# Charge.net
KiCad netlist of a schematic drawn in Altium Designer
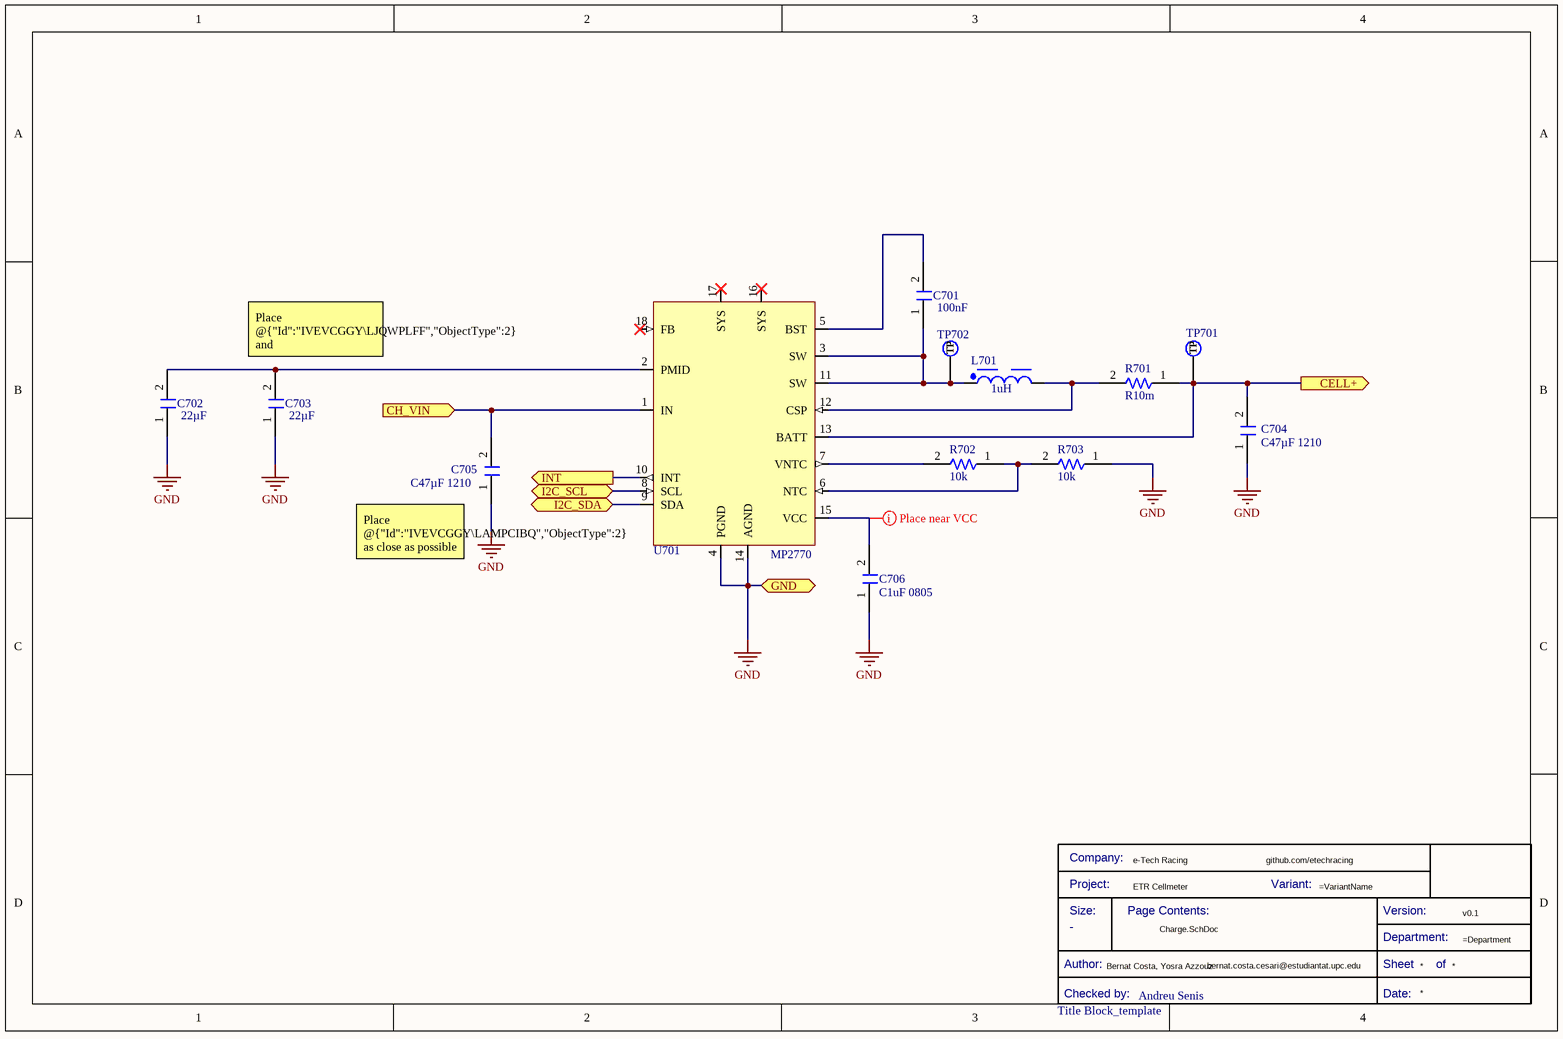
[diagram p0: Charge.SchDoc]

(export (version "E")
  (design (tool "Eeschema 10.0.6"))
  (components
    (comp (ref "*")
      (value "Title Block_template")
      (description "Standard Title Block")
      (fields
        (field (name "SIZE") "-")
        (field (name ".CREATOR") "GP")
        (field (name ".SCHCHECK") "GP")
        (field (name ".PCBCHECK") "GP")
      )
      (libsource (lib "EMEA- E-Tech Racing- I'Escola d'Enginyeria de Barcelona Est") (part "Title Block_template"))
    )
    (comp (ref "C701")
      (value "100nF")
      (footprint "CAPC1608X92X38LL15T08")
      (fields (field (name "Comment") "C100nF-25V-0603"))
      (libsource (lib "EMEA- E-Tech Racing- I'Escola d'Enginyeria de Barcelona Est") (part "C100p-50V-0805FNPC-C0G/NP0"))
    )
    (comp (ref "C702")
      (value "22µF")
      (footprint "WCAP-CSGP_0805_L2W1.25H0.8_Reflow")
      (fields (field (name "Comment") "C22uF-25V-0805"))
      (libsource (lib "EMEA- E-Tech Racing- I'Escola d'Enginyeria de Barcelona Est") (part "C100p-50V-0805FNPC-C0G/NP0"))
    )
    (comp (ref "C703")
      (value "22µF")
      (footprint "WCAP-CSGP_0805_L2W1.25H0.8_Reflow")
      (fields (field (name "Comment") "C22uF-25V-0805"))
      (libsource (lib "EMEA- E-Tech Racing- I'Escola d'Enginyeria de Barcelona Est") (part "C100p-50V-0805FNPC-C0G/NP0"))
    )
    (comp (ref "C704")
      (value "C47µF 1210")
      (footprint "FP-GRM32E-0_3-0_2-IPC_C")
      (libsource (lib "EMEA- E-Tech Racing- I'Escola d'Enginyeria de Barcelona Est") (part "C100p-50V-0805FNPC-C0G/NP0"))
    )
    (comp (ref "C705")
      (value "C47µF 1210")
      (footprint "FP-GRM32E-0_3-0_2-IPC_C")
      (libsource (lib "EMEA- E-Tech Racing- I'Escola d'Enginyeria de Barcelona Est") (part "C100p-50V-0805FNPC-C0G/NP0"))
    )
    (comp (ref "C706")
      (value "C1uF 0805")
      (footprint "WCAP-CSGP_0805_L2W1.25H1.25")
      (libsource (lib "EMEA- E-Tech Racing- I'Escola d'Enginyeria de Barcelona Est") (part "C100p-50V-0805FNPC-C0G/NP0"))
    )
    (comp (ref "L701")
      (value "1uH")
      (footprint "WE-PD_7345")
      (description "General Purpose Inductor, 1uH, 40%, 1 Element, Ferrite-Core, SMD, 2929. PN: 744777001")
      (fields (field (name "TOLERANCE") "40%") (field (name "Comment") "L1uH_120V_8A"))
      (libsource (lib "EMEA- E-Tech Racing- I'Escola d'Enginyeria de Barcelona Est") (part "Inductor - 2"))
    )
    (comp (ref "R701")
      (value "R10m")
      (footprint "WRIS-RSKS_1206_Wave")
      (fields
        (field (name "POWER") "250mW")
        (field (name "TOLERANCE") "1%")
        (field (name "Comment") "R10m-1206")
      )
      (libsource (lib "EMEA- E-Tech Racing- I'Escola d'Enginyeria de Barcelona Est") (part "R9.09K-1206FTK"))
    )
    (comp (ref "R702")
      (value "10k")
      (footprint "R0805FTK")
      (fields
        (field (name "TOLERANCE") "5%")
        (field (name "Comment") "R10k-0805FTK")
        (field (name ".CREATOR") "DR")
      )
      (libsource (lib "EMEA- E-Tech Racing- I'Escola d'Enginyeria de Barcelona Est") (part "R"))
    )
    (comp (ref "R703")
      (value "10k")
      (footprint "R0805FTK")
      (fields
        (field (name "TOLERANCE") "5%")
        (field (name "Comment") "R10k-0805FTK")
        (field (name ".CREATOR") "DR")
      )
      (libsource (lib "EMEA- E-Tech Racing- I'Escola d'Enginyeria de Barcelona Est") (part "R"))
    )
    (comp (ref "TP701")
      (value "TestPoint")
      (footprint "TestPoint")
      (description "Test Point 1x1 mm")
      (fields (field (name ".SCHCHECK") "GP") (field (name ".CREATOR") "GP") (field (name ".PCBCHECK") "GP"))
      (libsource (lib "EMEA- E-Tech Racing- I'Escola d'Enginyeria de Barcelona Est") (part "TestPoint"))
    )
    (comp (ref "TP702")
      (value "TestPoint")
      (footprint "TestPoint")
      (description "Test Point 1x1 mm")
      (fields (field (name ".SCHCHECK") "GP") (field (name ".CREATOR") "GP") (field (name ".PCBCHECK") "GP"))
      (libsource (lib "EMEA- E-Tech Racing- I'Escola d'Enginyeria de Barcelona Est") (part "TestPoint"))
    )
    (comp (ref "U701")
      (value "MP2770")
      (footprint "MP2770")
      (description "6A, 1-Cell Switching Charger with Power Path Management and 3.65A Boost Output")
      (libsource (lib "EMEA- E-Tech Racing- I'Escola d'Enginyeria de Barcelona Est") (part "MP2770"))
    )
  )
  (nets
    (net (code "1") (name "/CELL+") (class "Default")
      (node (ref "C704") (pin "2") (pinfunction "2_2") (pintype "passive"))
      (node (ref "R701") (pin "1") (pinfunction "1_1") (pintype "passive"))
      (node (ref "TP701") (pin "1") (pinfunction "TP_1") (pintype "passive"))
      (node (ref "U701") (pin "13") (pinfunction "BATT_13") (pintype "power_in"))
    )
    (net (code "2") (name "/CH_VIN") (class "Default")
      (node (ref "C705") (pin "2") (pinfunction "2_2") (pintype "passive"))
      (node (ref "U701") (pin "1") (pinfunction "IN_1") (pintype "power_in"))
    )
    (net (code "3") (name "/I2C_SCL") (class "Default")
      (node (ref "U701") (pin "8") (pinfunction "SCL_8") (pintype "input"))
    )
    (net (code "4") (name "/I2C_SDA") (class "Default")
      (node (ref "U701") (pin "9") (pinfunction "SDA_9") (pintype "bidirectional"))
    )
    (net (code "5") (name "/INT") (class "Default")
      (node (ref "U701") (pin "10") (pinfunction "INT_10") (pintype "output"))
    )
    (net (code "6") (name "GND") (class "Default")
      (node (ref "C702") (pin "1") (pinfunction "1_1") (pintype "passive"))
      (node (ref "C703") (pin "1") (pinfunction "1_1") (pintype "passive"))
      (node (ref "C704") (pin "1") (pinfunction "1_1") (pintype "passive"))
      (node (ref "C705") (pin "1") (pinfunction "1_1") (pintype "passive"))
      (node (ref "C706") (pin "1") (pinfunction "1_1") (pintype "passive"))
      (node (ref "R703") (pin "1") (pinfunction "1_1") (pintype "passive"))
      (node (ref "U701") (pin "14") (pinfunction "AGND_14") (pintype "power_in"))
      (node (ref "U701") (pin "4") (pinfunction "PGND_4") (pintype "power_in"))
    )
    (net (code "7") (name "Net-(TP702-TP)") (class "Default")
      (node (ref "C701") (pin "1") (pinfunction "1_1") (pintype "passive"))
      (node (ref "L701") (pin "1") (pinfunction "1_1") (pintype "passive"))
      (node (ref "TP702") (pin "1") (pinfunction "TP_1") (pintype "passive"))
      (node (ref "U701") (pin "11") (pinfunction "SW_11") (pintype "power_in"))
      (node (ref "U701") (pin "3") (pinfunction "SW_3") (pintype "power_in"))
    )
    (net (code "8") (name "Net-(U701-BST)") (class "Default")
      (node (ref "C701") (pin "2") (pinfunction "2_2") (pintype "passive"))
      (node (ref "U701") (pin "5") (pinfunction "BST_5") (pintype "power_in"))
    )
    (net (code "9") (name "Net-(U701-CSP)") (class "Default")
      (node (ref "L701") (pin "2") (pinfunction "2_2") (pintype "passive"))
      (node (ref "R701") (pin "2") (pinfunction "2_2") (pintype "passive"))
      (node (ref "U701") (pin "12") (pinfunction "CSP_12") (pintype "input"))
    )
    (net (code "10") (name "Net-(U701-NTC)") (class "Default")
      (node (ref "R702") (pin "1") (pinfunction "1_1") (pintype "passive"))
      (node (ref "R703") (pin "2") (pinfunction "2_2") (pintype "passive"))
      (node (ref "U701") (pin "6") (pinfunction "NTC_6") (pintype "input"))
    )
    (net (code "11") (name "Net-(U701-PMID)") (class "Default")
      (node (ref "C702") (pin "2") (pinfunction "2_2") (pintype "passive"))
      (node (ref "C703") (pin "2") (pinfunction "2_2") (pintype "passive"))
      (node (ref "U701") (pin "2") (pinfunction "PMID_2") (pintype "power_in"))
    )
    (net (code "12") (name "Net-(U701-VCC)") (class "Default")
      (node (ref "C706") (pin "2") (pinfunction "2_2") (pintype "passive"))
      (node (ref "U701") (pin "15") (pinfunction "VCC_15") (pintype "power_in"))
    )
    (net (code "13") (name "Net-(U701-VNTC)") (class "Default")
      (node (ref "R702") (pin "2") (pinfunction "2_2") (pintype "passive"))
      (node (ref "U701") (pin "7") (pinfunction "VNTC_7") (pintype "output"))
    )
    (net (code "14") (name "unconnected-(U701-FB-Pad18)") (class "Default")
      (node (ref "U701") (pin "18") (pinfunction "FB_18") (pintype "input+no_connect"))
    )
    (net (code "15") (name "unconnected-(U701-SYS-Pad16)") (class "Default")
      (node (ref "U701") (pin "16") (pinfunction "SYS_16") (pintype "power_in+no_connect"))
    )
    (net (code "16") (name "unconnected-(U701-SYS-Pad17)") (class "Default")
      (node (ref "U701") (pin "17") (pinfunction "SYS_17") (pintype "power_in+no_connect"))
    )
  )
)
